# EdgeMax_PowerSupply.net
KiCad netlist of a schematic drawn in Altium Designer
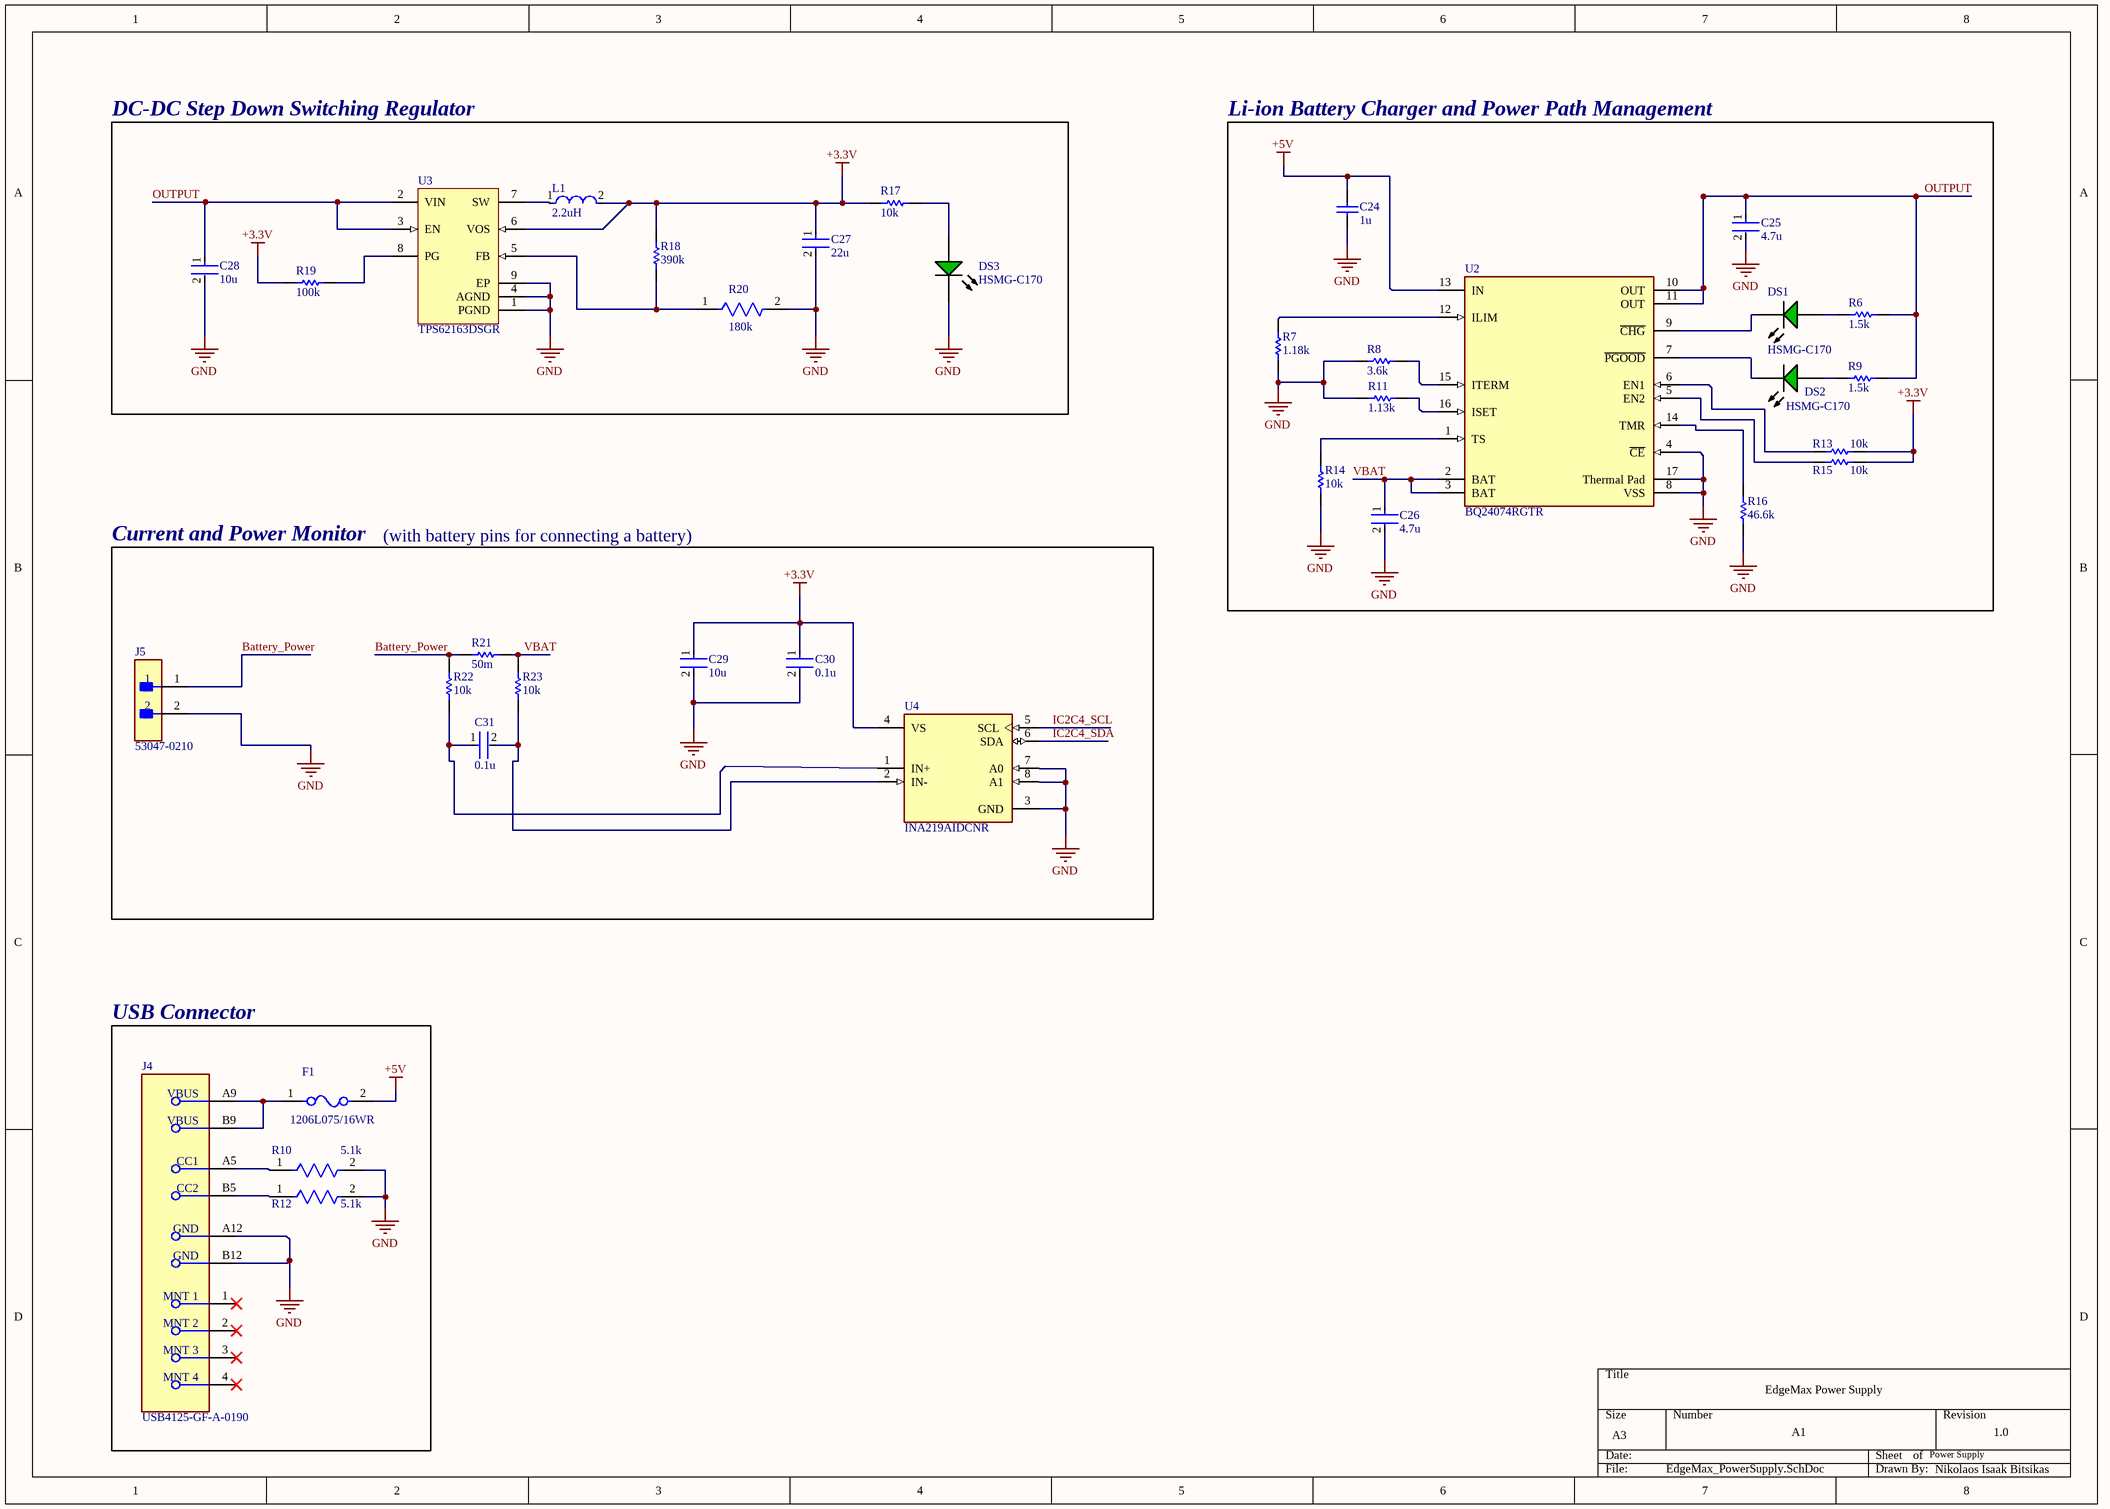
[diagram p0: EdgeMax_PowerSupply.SchDoc]

(export (version "E")
  (design (tool "Eeschema 10.0.6"))
  (components
    (comp (ref "C24")
      (value "1u")
      (footprint "CAPC1608X90X35LL15T15")
      (fields (field (name "MANUFACTURER") "Kemet") (field (name "PART NUMBER") "C0603C105K4RACTU"))
      (libsource (lib "Altium Content Vault") (part "CAP"))
    )
    (comp (ref "C25")
      (value "4.7u")
      (footprint "FP-CC1206-1_25-MFG")
      (description "CAP CER 4.7UF 50V X7R 1206")
      (fields (field (name "MANUFACTURER PART NUMBER") "CC1206KKX7R9BB475") (field (name "TOLERANCE") "0.1"))
      (libsource (lib "Altium Content Vault") (part "11868f565c42a9108669ba33697ecf6"))
    )
    (comp (ref "C26")
      (value "4.7u")
      (footprint "FP-CC1206-1_25-MFG")
      (description "CAP CER 4.7UF 50V X7R 1206")
      (fields (field (name "MANUFACTURER PART NUMBER") "CC1206KKX7R9BB475") (field (name "TOLERANCE") "0.1"))
      (libsource (lib "Altium Content Vault") (part "11868f565c42a9108669ba33697ecf6"))
    )
    (comp (ref "C27")
      (value "22u")
      (footprint "FP-C0805C226M9PACTU-MFG")
      (description "CAP CER 22UF 6.3V X5R 0805")
      (fields (field (name "TOLERANCE") "20%") (field (name "VOLTAGE") "6.3V"))
      (libsource (lib "Altium Content Vault") (part "11868f565c42a9108669ba33697ecf6"))
    )
    (comp (ref "C28")
      (value "10u")
      (footprint "FP-C0805C106K9PACTU-MFG")
      (description "CAP CER 10UF 6.3V X5R 0805")
      (fields (field (name "VOLTAGE") "6.3V") (field (name "TOLERANCE") "10%"))
      (libsource (lib "Altium Content Vault") (part "b4654b650e69147ec39a6b967a45e02"))
    )
    (comp (ref "C29")
      (value "10u")
      (footprint "FP-GRM21B-0_1-MFG")
      (description "Chip Multilayer Ceramic Capacitors for General Purpose, 0805, 10uF, X5R, 15%, 10%, 16V")
      (fields (field (name "TOLERANCE") "10%") (field (name "VOLTAGE") "16V"))
      (libsource (lib "Altium Content Vault") (part "b4654b650e69147ec39a6b967a45e02"))
    )
    (comp (ref "C30")
      (value "0.1u")
      (footprint "FP-C0402-BB-MFG")
      (description "CAP CER 0.1UF 16V X7R 0402")
      (fields
        (field (name "TOLERANCE") "0.1")
        (field (name "OCTOPART") "https://octopart.com/c0402c104k4ractu-kemet-94158")
      )
      (libsource (lib "Altium Content Vault") (part "b4654b650e69147ec39a6b967a45e02"))
    )
    (comp (ref "C31")
      (value "0.1u")
      (footprint "FP-C0402-BB-MFG")
      (description "CAP CER 0.1UF 10V X5R 0402")
      (fields (field (name "MANUFACTURER") "Kemet") (field (name "TOLERANCE") "0.1"))
      (libsource (lib "Altium Content Vault") (part "b4654b650e69147ec39a6b967a45e02"))
    )
    (comp (ref "DS1")
      (value "HSMG-C170")
      (footprint "AVAG-HSMX-C170_V")
      (description "Chip LED, Green, 2.2 V, -40 to 85 degC, 2-Pin SMD, Pb-Free, Tape and Reel")
      (fields (field (name "MANUFACTURER") "Avago"))
      (libsource (lib "Altium Content Vault") (part "LED_GREEN_A1K2-2"))
    )
    (comp (ref "DS2")
      (value "HSMG-C170")
      (footprint "AVAG-HSMX-C170_V")
      (description "Chip LED, Green, 2.2 V, -40 to 85 degC, 2-Pin SMD, Pb-Free, Tape and Reel")
      (fields (field (name "MANUFACTURER") "Avago"))
      (libsource (lib "Altium Content Vault") (part "LED_GREEN_A1K2-2"))
    )
    (comp (ref "DS3")
      (value "HSMG-C170")
      (footprint "AVAG-HSMX-C170_V")
      (description "Chip LED, Green, 2.2 V, -40 to 85 degC, 2-Pin SMD, Pb-Free, Tape and Reel")
      (fields (field (name "MANUFACTURER") "Avago"))
      (libsource (lib "Altium Content Vault") (part "LED_GREEN_A1K2-2"))
    )
    (comp (ref "F1")
      (value "1206L075/16WR")
      (footprint "FP-1206L-MFG")
      (description "PTC RESET FUSE 16V 750MA 1206")
      (fields
        (field (name "OCTOPART") "https://octopart.com/1206l075%2F16wr-littelfuse-28867102")
        (field (name "MANUFACTURER") "Littelfuse Inc")
      )
      (libsource (lib "Altium Content Vault") (part "5bcf9b9f640e542cf0359d10258e979"))
    )
    (comp (ref "J4")
      (value "USB4125-GF-A-0190")
      (footprint "FP-USB4125-GF-A-0190-MFG")
      (description "CONN RCPT TYPE C 6P SMD RA")
      (libsource (lib "Altium Content Vault") (part "a055484d46e58b234844902c9fd883a"))
    )
    (comp (ref "J5")
      (value "53047-0210")
      (footprint "FP-53047-0210-MFG")
      (description "CONN HEADER VERT 2POS 1.25MM")
      (fields
        (field (name "OCTOPART") "https://octopart.com/53047-0210-molex-276772")
        (field (name "MANUFACTURER") "Molex")
      )
      (libsource (lib "Altium Content Vault") (part "3bc925449376181038e59eaffc5286c"))
    )
    (comp (ref "L1")
      (value "2.2uH")
      (footprint "FP-CBMF1608-MFG")
      (description "SMD Inductors 2.2uH ±20% 0.56A 0.221Ω 0603")
      (fields (field (name "TOLERANCE") "20%"))
      (libsource (lib "Altium Content Vault") (part "725321dda6339637d4d059423bc1c3c"))
    )
    (comp (ref "R6")
      (value "1.5k")
      (footprint "RESC1005X40X25LL10T10")
      (fields (field (name "MANUFACTURER") "Panasonic") (field (name "PART NUMBER") "ERA2AEB152X"))
      (libsource (lib "Altium Content Vault") (part "RES"))
    )
    (comp (ref "R7")
      (value "1.18k")
      (footprint "RESC1609X50X30ML10T20")
      (fields (field (name "PART NUMBER") "CRCW06031K18FKEA") (field (name "MANUFACTURER") "Vishay Dale"))
      (libsource (lib "Altium Content Vault") (part "RES"))
    )
    (comp (ref "R8")
      (value "3.6k")
      (footprint "RESC1005X40X25ML05T05")
      (fields (field (name "MANUFACTURER") "Panasonic") (field (name "PART NUMBER") "ERJ-2RKF3601X"))
      (libsource (lib "Altium Content Vault") (part "RES"))
    )
    (comp (ref "R9")
      (value "1.5k")
      (footprint "RESC1005X40X25LL10T10")
      (fields (field (name "MANUFACTURER") "Panasonic") (field (name "PART NUMBER") "ERA2AEB152X"))
      (libsource (lib "Altium Content Vault") (part "RES"))
    )
    (comp (ref "R10")
      (value "5.1k")
      (footprint "FP-CRCW0603-e3-IPC_C")
      (description "RES Thick Film, 5.1kΩ, 1%, 0.1W, 100ppm/°C, 0603")
      (fields (field (name "TOLERANCE") "1%"))
      (libsource (lib "Altium Content Vault") (part "1029c3af85768c4190bb7ad29bc67b5"))
    )
    (comp (ref "R11")
      (value "1.13k")
      (footprint "RESC1005X40X25NL05T05")
      (fields (field (name "MANUFACTURER") "Panasonic") (field (name "PART NUMBER") "ERJ-2RKF1131X"))
      (libsource (lib "Altium Content Vault") (part "RES"))
    )
    (comp (ref "R12")
      (value "5.1k")
      (footprint "FP-CRCW0603-e3-IPC_C")
      (description "RES Thick Film, 5.1kΩ, 1%, 0.1W, 100ppm/°C, 0603")
      (fields (field (name "TOLERANCE") "1%"))
      (libsource (lib "Altium Content Vault") (part "1029c3af85768c4190bb7ad29bc67b5"))
    )
    (comp (ref "R13")
      (value "10k")
      (footprint "RESC2013X60X35NL10T20")
      (description "Chip Resistor, 10 KOhm, +/- 1%, 0.125 W, -55 to 155 degC, 0805 (2012 Metric), RoHS, Tape and Reel")
      (fields (field (name "MANUFACTURER") "Yageo"))
      (libsource (lib "Altium Content Vault") (part "RES-2"))
    )
    (comp (ref "R14")
      (value "10k")
      (footprint "RESC2013X60X35NL10T20")
      (description "Chip Resistor, 10 KOhm, +/- 1%, 0.125 W, -55 to 155 degC, 0805 (2012 Metric), RoHS, Tape and Reel")
      (fields (field (name "MANUFACTURER") "Yageo"))
      (libsource (lib "Altium Content Vault") (part "RES-2"))
    )
    (comp (ref "R15")
      (value "10k")
      (footprint "RESC2013X60X35NL10T20")
      (description "Chip Resistor, 10 KOhm, +/- 1%, 0.125 W, -55 to 155 degC, 0805 (2012 Metric), RoHS, Tape and Reel")
      (fields (field (name "MANUFACTURER") "Yageo"))
      (libsource (lib "Altium Content Vault") (part "RES-2"))
    )
    (comp (ref "R16")
      (value "46.6k")
      (footprint "RESC1608X55X30LL15T15")
      (fields (field (name "MANUFACTURER") "Panasonic") (field (name "PART NUMBER") "ERJ-3EKF4642V"))
      (libsource (lib "Altium Content Vault") (part "RES"))
    )
    (comp (ref "R17")
      (value "10k")
      (footprint "RESC2013X60X35NL10T20")
      (description "Chip Resistor, 10 KOhm, +/- 1%, 0.125 W, -55 to 155 degC, 0805 (2012 Metric), RoHS, Tape and Reel")
      (fields (field (name "MANUFACTURER") "Yageo"))
      (libsource (lib "Altium Content Vault") (part "RES-2"))
    )
    (comp (ref "R18")
      (value "390k")
      (footprint "RESC0603X26X15NL03T05")
      (fields (field (name "MANUFACTURER") "Panasonic") (field (name "PART NUMBER") "ERJ1GNF3903C"))
      (libsource (lib "Altium Content Vault") (part "RES"))
    )
    (comp (ref "R19")
      (value "100k")
      (footprint "RESC2013X50X30ML20T20")
      (fields (field (name "MANUFACTURER") "Vishay Dale") (field (name "PART NUMBER") "CRCW0805100KJNEA"))
      (libsource (lib "Altium Content Vault") (part "RES"))
    )
    (comp (ref "R20")
      (value "180k")
      (footprint "FP-CRCW0603-e3-IPC_A")
      (description "RES Thick Film, 180kΩ, 1%, 0.1W, 100ppm/°C, 0603")
      (fields (field (name "TOLERANCE") "1%"))
      (libsource (lib "Altium Content Vault") (part "1029c3af85768c4190bb7ad29bc67b5"))
    )
    (comp (ref "R21")
      (value "50m")
      (footprint "RESC3225X70X50NL20T20")
      (fields (field (name "PART NUMBER") "ERJ-L14KF50MU") (field (name "MANUFACTURER") "Panasonic"))
      (libsource (lib "Altium Content Vault") (part "RES"))
    )
    (comp (ref "R22")
      (value "10k")
      (footprint "RESC2013X50X30NL20T20")
      (fields (field (name "MANUFACTURER") "Vishay Dale") (field (name "PART NUMBER") "CRCW080510R0FKEA"))
      (libsource (lib "Altium Content Vault") (part "RES"))
    )
    (comp (ref "R23")
      (value "10k")
      (footprint "RESC2013X50X30NL20T20")
      (fields (field (name "MANUFACTURER") "Vishay Dale") (field (name "PART NUMBER") "CRCW080510R0FKEA"))
      (libsource (lib "Altium Content Vault") (part "RES"))
    )
    (comp (ref "U2")
      (value "BQ24074RGTR")
      (footprint "FP-RGT0016C-IPC_B")
      (description "IC LI-ION CHARGE MGMT 16-QFN")
      (libsource (lib "Altium Content Vault") (part "bc0294d1c007ba64400ebcffad863a1"))
    )
    (comp (ref "U3")
      (value "TPS62163DSGR")
      (footprint "DSG0008A_V")
      (fields (field (name "MANUFACTURER") "Texas Instruments"))
      (libsource (lib "Altium Content Vault") (part "TI-TPS62163DSG8-1600X900TP"))
    )
    (comp (ref "U4")
      (value "INA219AIDCNR")
      (footprint "FP-DCN0008A-IPC_B")
      (description "IC CURRENT MONITOR 1% SOT23-8")
      (libsource (lib "Altium Content Vault") (part "e16934b8ef90d0e345b266f0ae9cd81"))
    )
  )
  (nets
    (net (code "1") (name "+3.3V") (class "Default")
      (node (ref "C27") (pin "1") (pinfunction "1_1") (pintype "passive"))
      (node (ref "C29") (pin "1") (pinfunction "1_1") (pintype "passive"))
      (node (ref "C30") (pin "1") (pinfunction "1_1") (pintype "passive"))
      (node (ref "L1") (pin "2") (pinfunction "2_2") (pintype "passive"))
      (node (ref "R13") (pin "1") (pinfunction "1_1") (pintype "passive"))
      (node (ref "R15") (pin "1") (pinfunction "1_1") (pintype "passive"))
      (node (ref "R17") (pin "1") (pinfunction "1_1") (pintype "passive"))
      (node (ref "R18") (pin "2") (pinfunction "2_2") (pintype "passive"))
      (node (ref "R19") (pin "1") (pinfunction "1_1") (pintype "passive"))
      (node (ref "U3") (pin "6") (pinfunction "VOS_6") (pintype "input"))
      (node (ref "U4") (pin "4") (pinfunction "VS_4") (pintype "power_in"))
    )
    (net (code "2") (name "+5V") (class "Default")
      (node (ref "C24") (pin "2") (pinfunction "2_2") (pintype "passive"))
      (node (ref "F1") (pin "2") (pinfunction "2_2") (pintype "passive"))
      (node (ref "U2") (pin "13") (pinfunction "IN_13") (pintype "power_in"))
    )
    (net (code "3") (name "/Battery_Power") (class "Default")
      (node (ref "J5") (pin "1") (pinfunction "1_1") (pintype "passive"))
      (node (ref "R21") (pin "1") (pinfunction "1_1") (pintype "passive"))
      (node (ref "R22") (pin "2") (pinfunction "2_2") (pintype "passive"))
    )
    (net (code "4") (name "/IC2C4_SCL") (class "Default")
      (node (ref "U4") (pin "5") (pinfunction "SCL_5") (pintype "input"))
    )
    (net (code "5") (name "/IC2C4_SDA") (class "Default")
      (node (ref "U4") (pin "6") (pinfunction "SDA_6") (pintype "bidirectional"))
    )
    (net (code "6") (name "/OUTPUT") (class "Default")
      (node (ref "C25") (pin "1") (pinfunction "1_1") (pintype "passive"))
      (node (ref "C28") (pin "1") (pinfunction "1_1") (pintype "passive"))
      (node (ref "R6") (pin "2") (pinfunction "2_2") (pintype "passive"))
      (node (ref "R9") (pin "2") (pinfunction "2_2") (pintype "passive"))
      (node (ref "U2") (pin "10") (pinfunction "OUT_10") (pintype "power_in"))
      (node (ref "U2") (pin "11") (pinfunction "OUT_11") (pintype "power_in"))
      (node (ref "U3") (pin "2") (pinfunction "VIN_2") (pintype "power_in"))
      (node (ref "U3") (pin "3") (pinfunction "EN_3") (pintype "input"))
    )
    (net (code "7") (name "/VBAT") (class "Default")
      (node (ref "C26") (pin "1") (pinfunction "1_1") (pintype "passive"))
      (node (ref "R21") (pin "2") (pinfunction "2_2") (pintype "passive"))
      (node (ref "R23") (pin "2") (pinfunction "2_2") (pintype "passive"))
      (node (ref "U2") (pin "2") (pinfunction "BAT_2") (pintype "power_in"))
      (node (ref "U2") (pin "3") (pinfunction "BAT_3") (pintype "power_in"))
    )
    (net (code "8") (name "GND") (class "Default")
      (node (ref "C24") (pin "1") (pinfunction "1_1") (pintype "passive"))
      (node (ref "C25") (pin "2") (pinfunction "2_2") (pintype "passive"))
      (node (ref "C26") (pin "2") (pinfunction "2_2") (pintype "passive"))
      (node (ref "C27") (pin "2") (pinfunction "2_2") (pintype "passive"))
      (node (ref "C28") (pin "2") (pinfunction "2_2") (pintype "passive"))
      (node (ref "C29") (pin "2") (pinfunction "2_2") (pintype "passive"))
      (node (ref "C30") (pin "2") (pinfunction "2_2") (pintype "passive"))
      (node (ref "DS3") (pin "2") (pinfunction "K_2") (pintype "passive"))
      (node (ref "J4") (pin "A12") (pinfunction "GND_A12") (pintype "passive"))
      (node (ref "J4") (pin "B12") (pinfunction "GND_B12") (pintype "passive"))
      (node (ref "J5") (pin "2") (pinfunction "2_2") (pintype "passive"))
      (node (ref "R10") (pin "2") (pinfunction "2_2") (pintype "passive"))
      (node (ref "R11") (pin "2") (pinfunction "2_2") (pintype "passive"))
      (node (ref "R12") (pin "2") (pinfunction "2_2") (pintype "passive"))
      (node (ref "R14") (pin "1") (pinfunction "1_1") (pintype "passive"))
      (node (ref "R16") (pin "1") (pinfunction "1_1") (pintype "passive"))
      (node (ref "R20") (pin "2") (pinfunction "2_2") (pintype "passive"))
      (node (ref "R7") (pin "1") (pinfunction "1_1") (pintype "passive"))
      (node (ref "R8") (pin "2") (pinfunction "2_2") (pintype "passive"))
      (node (ref "U2") (pin "17") (pinfunction "Thermal_Pad_17") (pintype "power_in"))
      (node (ref "U2") (pin "4") (pinfunction "~{CE}_4") (pintype "input"))
      (node (ref "U2") (pin "8") (pinfunction "VSS_8") (pintype "power_in"))
      (node (ref "U3") (pin "1") (pinfunction "PGND_1") (pintype "power_in"))
      (node (ref "U3") (pin "4") (pinfunction "AGND_4") (pintype "power_in"))
      (node (ref "U3") (pin "9") (pinfunction "EP_9") (pintype "power_in"))
      (node (ref "U4") (pin "3") (pinfunction "GND_3") (pintype "power_in"))
      (node (ref "U4") (pin "7") (pinfunction "A0_7") (pintype "input"))
      (node (ref "U4") (pin "8") (pinfunction "A1_8") (pintype "input"))
    )
    (net (code "9") (name "Net-(DS1-A)") (class "Default")
      (node (ref "DS1") (pin "1") (pinfunction "A_1") (pintype "passive"))
      (node (ref "R6") (pin "1") (pinfunction "1_1") (pintype "passive"))
    )
    (net (code "10") (name "Net-(DS1-K)") (class "Default")
      (node (ref "DS1") (pin "2") (pinfunction "K_2") (pintype "passive"))
      (node (ref "U2") (pin "9") (pinfunction "~{CHG}_9") (pintype "tri_state"))
    )
    (net (code "11") (name "Net-(DS2-A)") (class "Default")
      (node (ref "DS2") (pin "1") (pinfunction "A_1") (pintype "passive"))
      (node (ref "R9") (pin "1") (pinfunction "1_1") (pintype "passive"))
    )
    (net (code "12") (name "Net-(DS2-K)") (class "Default")
      (node (ref "DS2") (pin "2") (pinfunction "K_2") (pintype "passive"))
      (node (ref "U2") (pin "7") (pinfunction "~{PGOOD}_7") (pintype "tri_state"))
    )
    (net (code "13") (name "Net-(DS3-A)") (class "Default")
      (node (ref "DS3") (pin "1") (pinfunction "A_1") (pintype "passive"))
      (node (ref "R17") (pin "2") (pinfunction "2_2") (pintype "passive"))
    )
    (net (code "14") (name "Net-(F1-Pad1)") (class "Default")
      (node (ref "F1") (pin "1") (pinfunction "1_1") (pintype "passive"))
      (node (ref "J4") (pin "A9") (pinfunction "VBUS_A9") (pintype "passive"))
      (node (ref "J4") (pin "B9") (pinfunction "VBUS_B9") (pintype "passive"))
    )
    (net (code "15") (name "Net-(J4-CC1)") (class "Default")
      (node (ref "J4") (pin "A5") (pinfunction "CC1_A5") (pintype "passive"))
      (node (ref "R10") (pin "1") (pinfunction "1_1") (pintype "passive"))
    )
    (net (code "16") (name "Net-(J4-CC2)") (class "Default")
      (node (ref "J4") (pin "B5") (pinfunction "CC2_B5") (pintype "passive"))
      (node (ref "R12") (pin "1") (pinfunction "1_1") (pintype "passive"))
    )
    (net (code "17") (name "Net-(U2-EN1)") (class "Default")
      (node (ref "R13") (pin "2") (pinfunction "2_2") (pintype "passive"))
      (node (ref "U2") (pin "6") (pinfunction "EN1_6") (pintype "input"))
    )
    (net (code "18") (name "Net-(U2-EN2)") (class "Default")
      (node (ref "R15") (pin "2") (pinfunction "2_2") (pintype "passive"))
      (node (ref "U2") (pin "5") (pinfunction "EN2_5") (pintype "input"))
    )
    (net (code "19") (name "Net-(U2-ILIM)") (class "Default")
      (node (ref "R7") (pin "2") (pinfunction "2_2") (pintype "passive"))
      (node (ref "U2") (pin "12") (pinfunction "ILIM_12") (pintype "input"))
    )
    (net (code "20") (name "Net-(U2-ISET)") (class "Default")
      (node (ref "R11") (pin "1") (pinfunction "1_1") (pintype "passive"))
      (node (ref "U2") (pin "16") (pinfunction "ISET_16") (pintype "input"))
    )
    (net (code "21") (name "Net-(U2-ITERM)") (class "Default")
      (node (ref "R8") (pin "1") (pinfunction "1_1") (pintype "passive"))
      (node (ref "U2") (pin "15") (pinfunction "ITERM_15") (pintype "input"))
    )
    (net (code "22") (name "Net-(U2-TMR)") (class "Default")
      (node (ref "R16") (pin "2") (pinfunction "2_2") (pintype "passive"))
      (node (ref "U2") (pin "14") (pinfunction "TMR_14") (pintype "input"))
    )
    (net (code "23") (name "Net-(U2-TS)") (class "Default")
      (node (ref "R14") (pin "2") (pinfunction "2_2") (pintype "passive"))
      (node (ref "U2") (pin "1") (pinfunction "TS_1") (pintype "input"))
    )
    (net (code "24") (name "Net-(U3-FB)") (class "Default")
      (node (ref "R18") (pin "1") (pinfunction "1_1") (pintype "passive"))
      (node (ref "R20") (pin "1") (pinfunction "1_1") (pintype "passive"))
      (node (ref "U3") (pin "5") (pinfunction "FB_5") (pintype "input"))
    )
    (net (code "25") (name "Net-(U3-PG)") (class "Default")
      (node (ref "R19") (pin "2") (pinfunction "2_2") (pintype "passive"))
      (node (ref "U3") (pin "8") (pinfunction "PG_8") (pintype "tri_state"))
    )
    (net (code "26") (name "Net-(U3-SW)") (class "Default")
      (node (ref "L1") (pin "1") (pinfunction "1_1") (pintype "passive"))
      (node (ref "U3") (pin "7") (pinfunction "SW_7") (pintype "power_in"))
    )
    (net (code "27") (name "Net-(U4-IN+)") (class "Default")
      (node (ref "C31") (pin "1") (pinfunction "1_1") (pintype "passive"))
      (node (ref "R22") (pin "1") (pinfunction "1_1") (pintype "passive"))
      (node (ref "U4") (pin "1") (pinfunction "IN+_1") (pintype "passive"))
    )
    (net (code "28") (name "Net-(U4-IN-)") (class "Default")
      (node (ref "C31") (pin "2") (pinfunction "2_2") (pintype "passive"))
      (node (ref "R23") (pin "1") (pinfunction "1_1") (pintype "passive"))
      (node (ref "U4") (pin "2") (pinfunction "IN-_2") (pintype "input"))
    )
    (net (code "29") (name "unconnected-(J4-MNT_1-Pad1)") (class "Default")
      (node (ref "J4") (pin "1") (pinfunction "MNT_1_1") (pintype "passive+no_connect"))
    )
    (net (code "30") (name "unconnected-(J4-MNT_2-Pad2)") (class "Default")
      (node (ref "J4") (pin "2") (pinfunction "MNT_2_2") (pintype "passive+no_connect"))
    )
    (net (code "31") (name "unconnected-(J4-MNT_3-Pad3)") (class "Default")
      (node (ref "J4") (pin "3") (pinfunction "MNT_3_3") (pintype "passive+no_connect"))
    )
    (net (code "32") (name "unconnected-(J4-MNT_4-Pad4)") (class "Default")
      (node (ref "J4") (pin "4") (pinfunction "MNT_4_4") (pintype "passive+no_connect"))
    )
  )
)
